# output_headers.net
KiCad netlist of a schematic drawn in Altium Designer
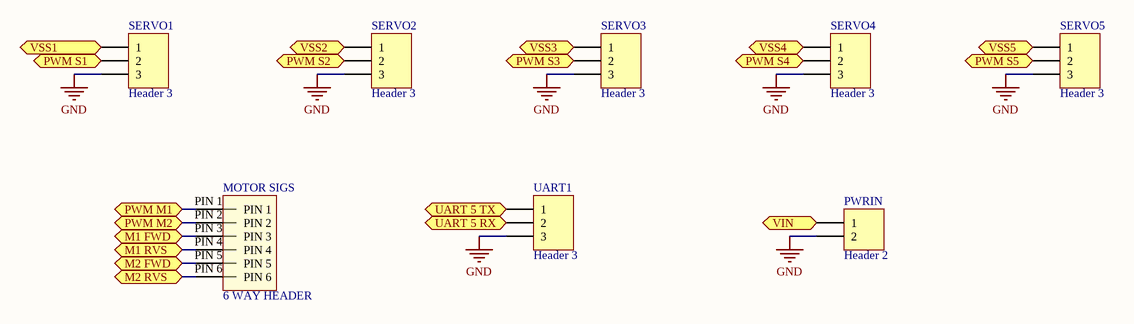
[diagram p0: output_headers.SchDoc]

(export (version "E")
  (design (tool "Eeschema 10.0.6"))
  (components
    (comp (ref "MOTOR SIGS")
      (value "6 WAY HEADER")
      (footprint "PH CONNECTOR 6 WAY")
      (libsource (lib "PH_HEADER_6_WAY") (part "PH HEADER 6 WAY"))
    )
    (comp (ref "PWRIN")
      (value "Header 2")
      (footprint "HDR1X2")
      (description "Header, 2-Pin")
      (fields (field (name "PUBLISHER") "Altium Limited"))
      (libsource (lib "Miscellaneous Connectors") (part "Header 2"))
    )
    (comp (ref "SERVO1")
      (value "Header 3")
      (footprint "HDR1X3")
      (description "Header, 3-Pin")
      (fields (field (name "PUBLISHER") "Altium Limited"))
      (libsource (lib "Miscellaneous Connectors") (part "Header 3"))
    )
    (comp (ref "SERVO2")
      (value "Header 3")
      (footprint "HDR1X3")
      (description "Header, 3-Pin")
      (fields (field (name "PUBLISHER") "Altium Limited"))
      (libsource (lib "Miscellaneous Connectors") (part "Header 3"))
    )
    (comp (ref "SERVO3")
      (value "Header 3")
      (footprint "HDR1X3")
      (description "Header, 3-Pin")
      (fields (field (name "PUBLISHER") "Altium Limited"))
      (libsource (lib "Miscellaneous Connectors") (part "Header 3"))
    )
    (comp (ref "SERVO4")
      (value "Header 3")
      (footprint "HDR1X3")
      (description "Header, 3-Pin")
      (fields (field (name "PUBLISHER") "Altium Limited"))
      (libsource (lib "Miscellaneous Connectors") (part "Header 3"))
    )
    (comp (ref "SERVO5")
      (value "Header 3")
      (footprint "HDR1X3")
      (description "Header, 3-Pin")
      (fields (field (name "PUBLISHER") "Altium Limited"))
      (libsource (lib "Miscellaneous Connectors") (part "Header 3"))
    )
    (comp (ref "UART1")
      (value "Header 3")
      (footprint "HDR1X3")
      (description "Header, 3-Pin")
      (fields (field (name "PUBLISHER") "Altium Limited"))
      (libsource (lib "Miscellaneous Connectors") (part "Header 3"))
    )
  )
  (nets
    (net (code "1") (name "/M1 FWD") (class "Default")
      (node (ref "MOTOR SIGS") (pin "PIN_3") (pinfunction "PIN_3_PIN_3") (pintype "passive"))
    )
    (net (code "2") (name "/M1 RVS") (class "Default")
      (node (ref "MOTOR SIGS") (pin "PIN_4") (pinfunction "PIN_4_PIN_4") (pintype "passive"))
    )
    (net (code "3") (name "/M2 FWD") (class "Default")
      (node (ref "MOTOR SIGS") (pin "PIN_5") (pinfunction "PIN_5_PIN_5") (pintype "passive"))
    )
    (net (code "4") (name "/M2 RVS") (class "Default")
      (node (ref "MOTOR SIGS") (pin "PIN_6") (pinfunction "PIN_6_PIN_6") (pintype "passive"))
    )
    (net (code "5") (name "/PWM M1") (class "Default")
      (node (ref "MOTOR SIGS") (pin "PIN_1") (pinfunction "PIN_1_PIN_1") (pintype "passive"))
    )
    (net (code "6") (name "/PWM M2") (class "Default")
      (node (ref "MOTOR SIGS") (pin "PIN_2") (pinfunction "PIN_2_PIN_2") (pintype "passive"))
    )
    (net (code "7") (name "/PWM S1") (class "Default")
      (node (ref "SERVO1") (pin "2") (pinfunction "2_2") (pintype "passive"))
    )
    (net (code "8") (name "/PWM S2") (class "Default")
      (node (ref "SERVO2") (pin "2") (pinfunction "2_2") (pintype "passive"))
    )
    (net (code "9") (name "/PWM S3") (class "Default")
      (node (ref "SERVO3") (pin "2") (pinfunction "2_2") (pintype "passive"))
    )
    (net (code "10") (name "/PWM S4") (class "Default")
      (node (ref "SERVO4") (pin "2") (pinfunction "2_2") (pintype "passive"))
    )
    (net (code "11") (name "/PWM S5") (class "Default")
      (node (ref "SERVO5") (pin "2") (pinfunction "2_2") (pintype "passive"))
    )
    (net (code "12") (name "/UART 5 RX") (class "Default")
      (node (ref "UART1") (pin "2") (pinfunction "2_2") (pintype "passive"))
    )
    (net (code "13") (name "/UART 5 TX") (class "Default")
      (node (ref "UART1") (pin "1") (pinfunction "1_1") (pintype "passive"))
    )
    (net (code "14") (name "/VIN") (class "Default")
      (node (ref "PWRIN") (pin "1") (pinfunction "1_1") (pintype "passive"))
    )
    (net (code "15") (name "/VSS1") (class "Default")
      (node (ref "SERVO1") (pin "1") (pinfunction "1_1") (pintype "passive"))
    )
    (net (code "16") (name "/VSS2") (class "Default")
      (node (ref "SERVO2") (pin "1") (pinfunction "1_1") (pintype "passive"))
    )
    (net (code "17") (name "/VSS3") (class "Default")
      (node (ref "SERVO3") (pin "1") (pinfunction "1_1") (pintype "passive"))
    )
    (net (code "18") (name "/VSS4") (class "Default")
      (node (ref "SERVO4") (pin "1") (pinfunction "1_1") (pintype "passive"))
    )
    (net (code "19") (name "/VSS5") (class "Default")
      (node (ref "SERVO5") (pin "1") (pinfunction "1_1") (pintype "passive"))
    )
    (net (code "20") (name "GND") (class "Default")
      (node (ref "PWRIN") (pin "2") (pinfunction "2_2") (pintype "passive"))
      (node (ref "SERVO1") (pin "3") (pinfunction "3_3") (pintype "passive"))
      (node (ref "SERVO2") (pin "3") (pinfunction "3_3") (pintype "passive"))
      (node (ref "SERVO3") (pin "3") (pinfunction "3_3") (pintype "passive"))
      (node (ref "SERVO4") (pin "3") (pinfunction "3_3") (pintype "passive"))
      (node (ref "SERVO5") (pin "3") (pinfunction "3_3") (pintype "passive"))
      (node (ref "UART1") (pin "3") (pinfunction "3_3") (pintype "passive"))
    )
  )
)
